# power_distribution_board_v3.net
KiCad netlist of a schematic drawn in EasyEDA
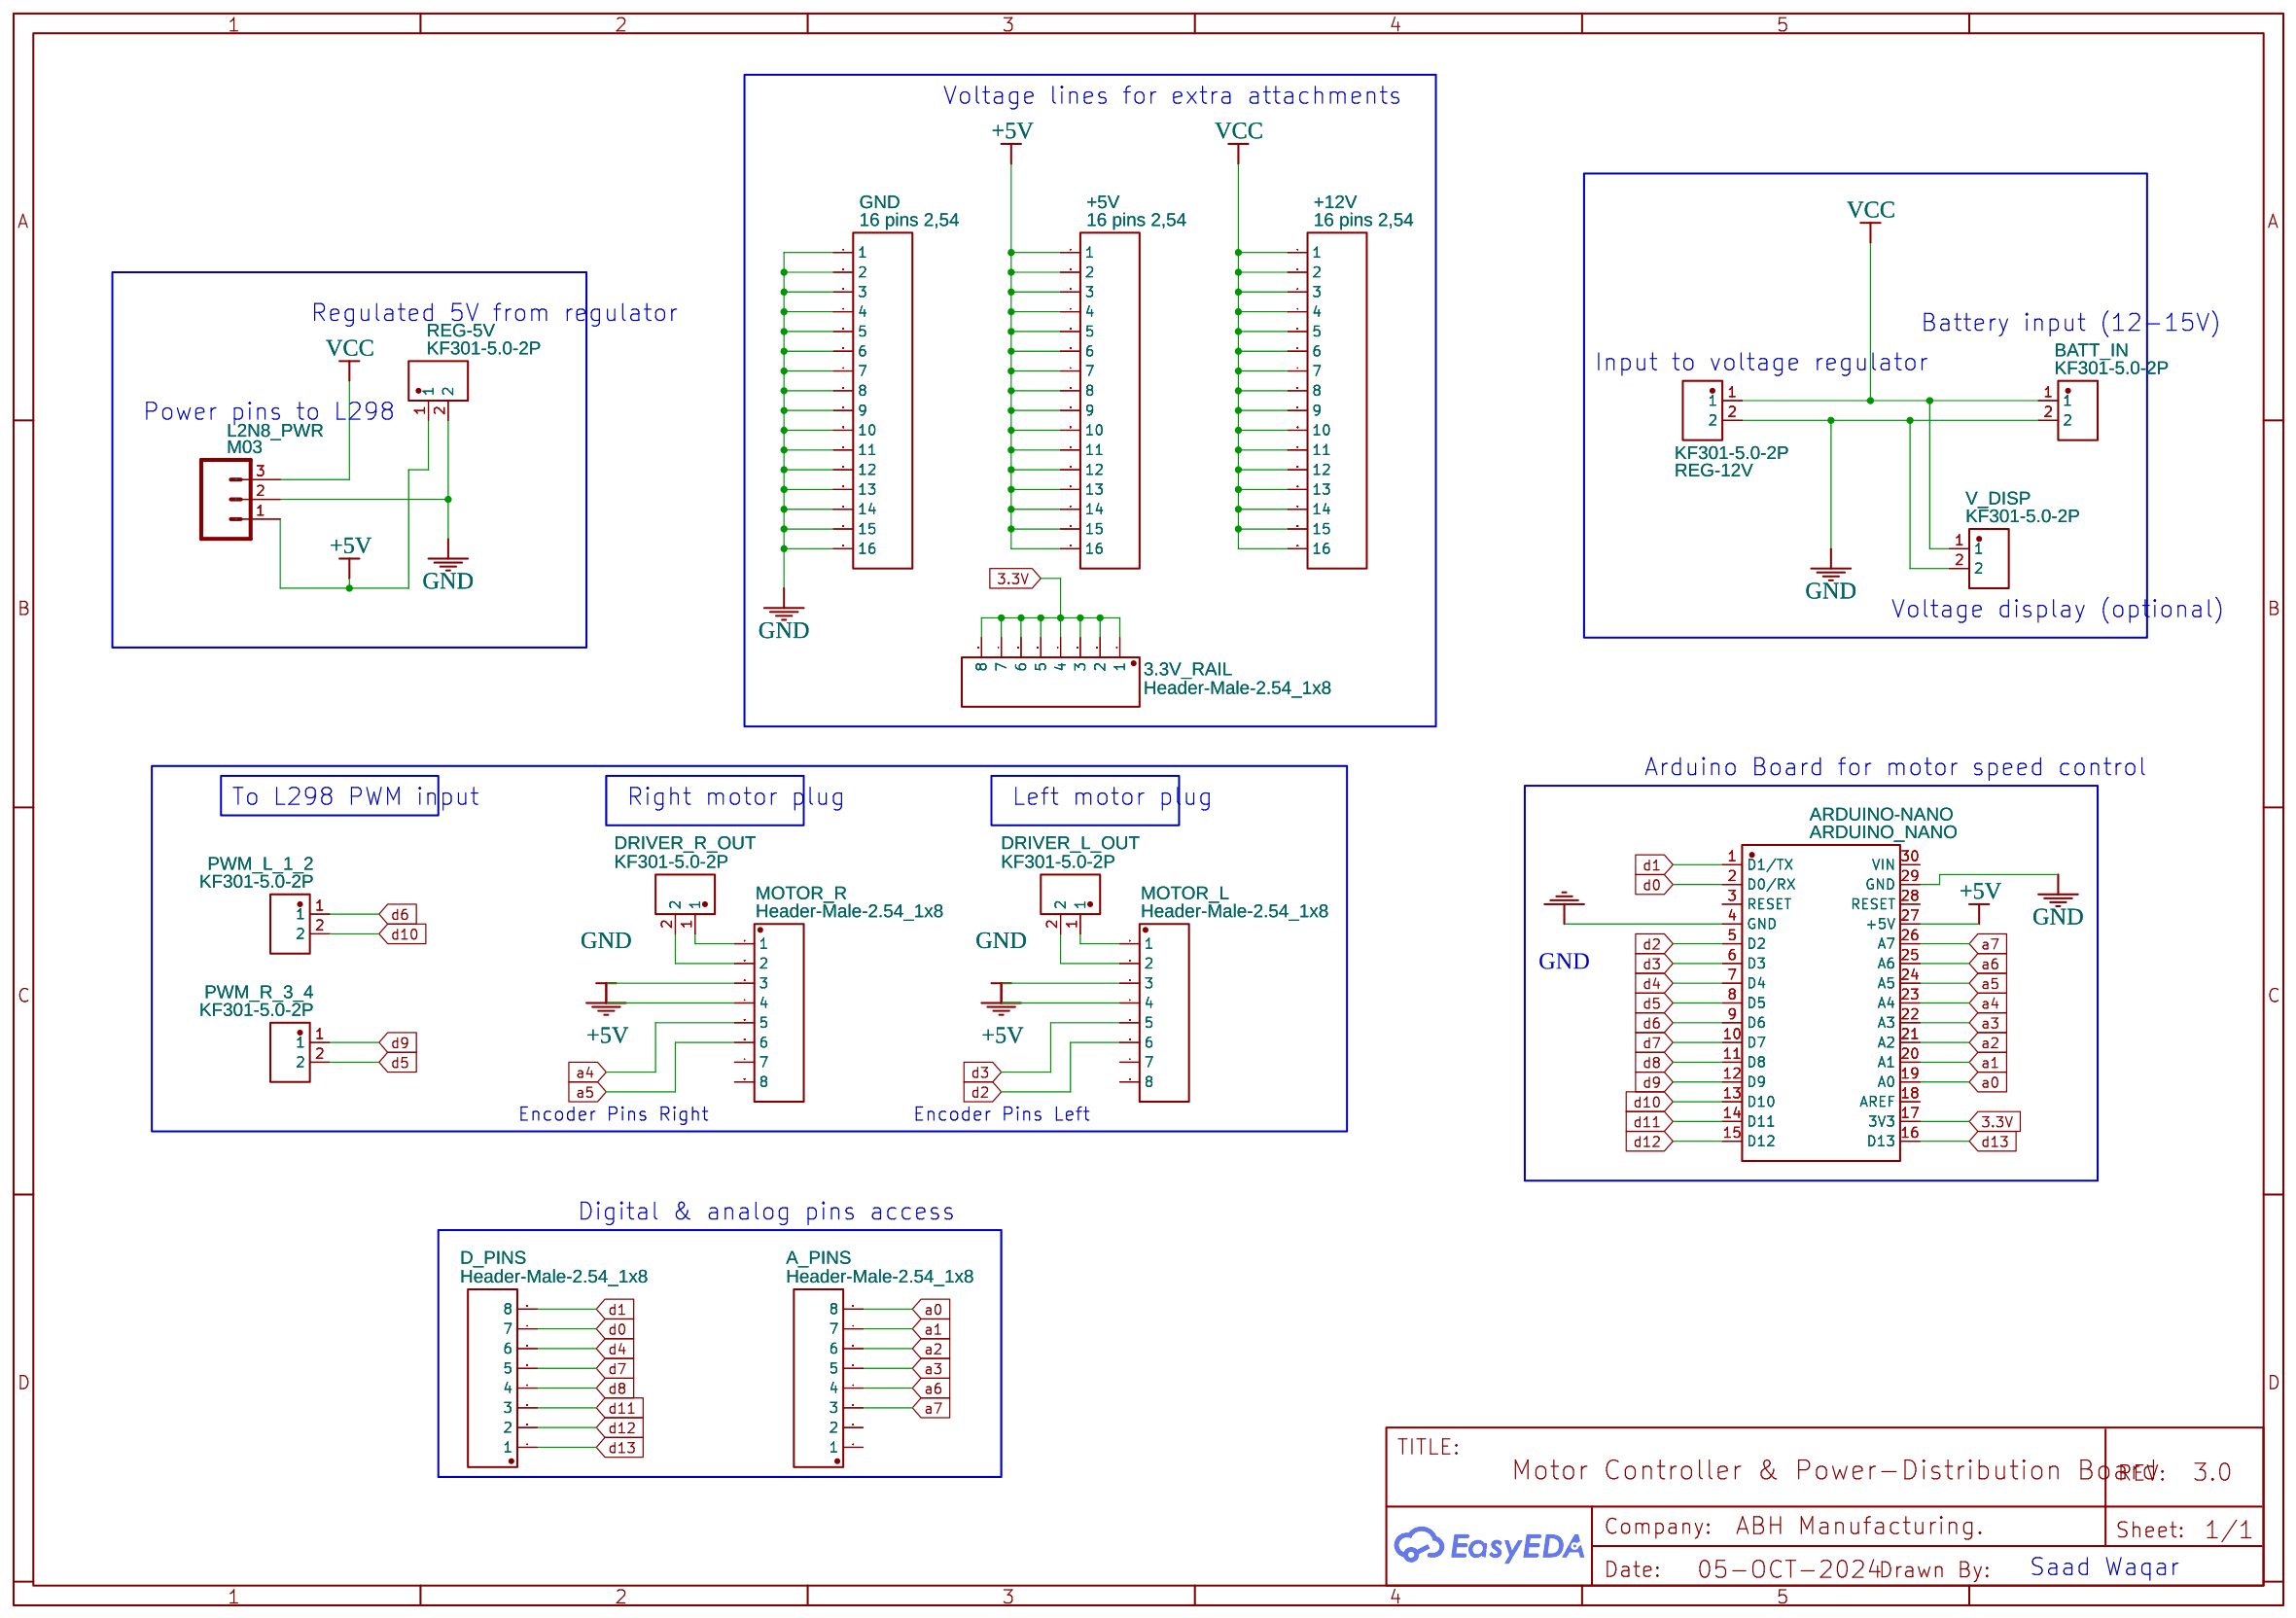
[diagram p0: schematic sheet]

(export (version "E")
  (design (tool "Eeschema 10.0.6"))
  (components
    (comp (ref "+5V") (value "16 pins 2,54") (libsource (lib "") (part "16 pins 2,54_1")))
    (comp (ref "+12V") (value "16 pins 2,54") (libsource (lib "") (part "16 pins 2,54_2")))
    (comp (ref "3.3V_RAIL")
      (value "Header-Male-2.54_1x8")
      (fields (field (name "Manufacturer Part") "B-2100S08P-A110") (field (name "Manufacturer") "Ckmtw(灿科盟)"))
      (libsource (lib "") (part "Header-Male-2.54_1x8_1"))
    )
    (comp (ref "ARDUINO-NANO") (value "ARDUINO_NANO") (libsource (lib "") (part "ARDUINO_NANO")))
    (comp (ref "A_PINS")
      (value "Header-Male-2.54_1x8")
      (fields (field (name "Manufacturer Part") "B-2100S08P-A110") (field (name "Manufacturer") "Ckmtw(灿科盟)"))
      (libsource (lib "") (part "Header-Male-2.54_1x8_2"))
    )
    (comp (ref "BATT_IN")
      (value "KF301-5.0-2P")
      (fields (field (name "Manufacturer") "KEFA(科发)"))
      (libsource (lib "") (part "KF301-5.0-2P_6"))
    )
    (comp (ref "DRIVER_L_OUT")
      (value "KF301-5.0-2P")
      (fields (field (name "Manufacturer") "KEFA(科发)"))
      (libsource (lib "") (part "KF301-5.0-2P_1"))
    )
    (comp (ref "DRIVER_R_OUT")
      (value "KF301-5.0-2P")
      (fields (field (name "Manufacturer") "KEFA(科发)"))
      (libsource (lib "") (part "KF301-5.0-2P_5"))
    )
    (comp (ref "D_PINS")
      (value "Header-Male-2.54_1x8")
      (fields (field (name "Manufacturer Part") "B-2100S08P-A110") (field (name "Manufacturer") "Ckmtw(灿科盟)"))
      (libsource (lib "") (part "Header-Male-2.54_1x8_4"))
    )
    (comp (ref "GND") (value "16 pins 2,54") (libsource (lib "") (part "16 pins 2,54")))
    (comp (ref "L2N8_PWR") (value "M03") (libsource (lib "") (part "M03")))
    (comp (ref "MOTOR_L")
      (value "Header-Male-2.54_1x8")
      (fields (field (name "Manufacturer Part") "B-2100S08P-A110") (field (name "Manufacturer") "Ckmtw(灿科盟)"))
      (libsource (lib "") (part "Header-Male-2.54_1x8_3"))
    )
    (comp (ref "MOTOR_R")
      (value "Header-Male-2.54_1x8")
      (fields (field (name "Manufacturer Part") "B-2100S08P-A110") (field (name "Manufacturer") "Ckmtw(灿科盟)"))
      (libsource (lib "") (part "Header-Male-2.54_1x8"))
    )
    (comp (ref "PWM_L_1_2")
      (value "KF301-5.0-2P")
      (fields (field (name "Manufacturer") "KEFA(科发)"))
      (libsource (lib "") (part "KF301-5.0-2P_2"))
    )
    (comp (ref "PWM_R_3_4")
      (value "KF301-5.0-2P")
      (fields (field (name "Manufacturer") "KEFA(科发)"))
      (libsource (lib "") (part "KF301-5.0-2P_4"))
    )
    (comp (ref "REG-5V")
      (value "KF301-5.0-2P")
      (fields (field (name "Manufacturer") "KEFA(科发)"))
      (libsource (lib "") (part "KF301-5.0-2P"))
    )
    (comp (ref "REG-12V")
      (value "KF301-5.0-2P")
      (fields (field (name "Manufacturer") "KEFA(科发)"))
      (libsource (lib "") (part "KF301-5.0-2P_3"))
    )
    (comp (ref "V_DISP")
      (value "KF301-5.0-2P")
      (fields (field (name "Manufacturer") "KEFA(科发)"))
      (libsource (lib "") (part "KF301-5.0-2P_7"))
    )
  )
  (nets
    (net (code "1") (name "+5V") (class "Default")
      (node (ref "+5V") (pin "1") (pinfunction "1_1") (pintype "input"))
      (node (ref "+5V") (pin "10") (pinfunction "10_10") (pintype "input"))
      (node (ref "+5V") (pin "11") (pinfunction "11_11") (pintype "input"))
      (node (ref "+5V") (pin "12") (pinfunction "12_12") (pintype "input"))
      (node (ref "+5V") (pin "13") (pinfunction "13_13") (pintype "input"))
      (node (ref "+5V") (pin "14") (pinfunction "14_14") (pintype "input"))
      (node (ref "+5V") (pin "15") (pinfunction "15_15") (pintype "input"))
      (node (ref "+5V") (pin "16") (pinfunction "16_16") (pintype "input"))
      (node (ref "+5V") (pin "2") (pinfunction "2_2") (pintype "input"))
      (node (ref "+5V") (pin "3") (pinfunction "3_3") (pintype "input"))
      (node (ref "+5V") (pin "4") (pinfunction "4_4") (pintype "input"))
      (node (ref "+5V") (pin "5") (pinfunction "5_5") (pintype "input"))
      (node (ref "+5V") (pin "6") (pinfunction "6_6") (pintype "input"))
      (node (ref "+5V") (pin "7") (pinfunction "7_7") (pintype "input"))
      (node (ref "+5V") (pin "8") (pinfunction "8_8") (pintype "input"))
      (node (ref "+5V") (pin "9") (pinfunction "9_9") (pintype "input"))
      (node (ref "ARDUINO-NANO") (pin "27") (pinfunction "+5V_27") (pintype "unspecified"))
      (node (ref "L2N8_PWR") (pin "1") (pinfunction "1_1") (pintype "unspecified"))
      (node (ref "MOTOR_L") (pin "4") (pinfunction "4_4") (pintype "unspecified"))
      (node (ref "MOTOR_R") (pin "4") (pinfunction "4_4") (pintype "unspecified"))
      (node (ref "REG-5V") (pin "1") (pinfunction "1_1") (pintype "unspecified"))
    )
    (net (code "2") (name "3.3V") (class "Default")
      (node (ref "3.3V_RAIL") (pin "1") (pinfunction "1_1") (pintype "unspecified"))
      (node (ref "3.3V_RAIL") (pin "2") (pinfunction "2_2") (pintype "unspecified"))
      (node (ref "3.3V_RAIL") (pin "3") (pinfunction "3_3") (pintype "unspecified"))
      (node (ref "3.3V_RAIL") (pin "4") (pinfunction "4_4") (pintype "unspecified"))
      (node (ref "3.3V_RAIL") (pin "5") (pinfunction "5_5") (pintype "unspecified"))
      (node (ref "3.3V_RAIL") (pin "6") (pinfunction "6_6") (pintype "unspecified"))
      (node (ref "3.3V_RAIL") (pin "7") (pinfunction "7_7") (pintype "unspecified"))
      (node (ref "3.3V_RAIL") (pin "8") (pinfunction "8_8") (pintype "unspecified"))
      (node (ref "ARDUINO-NANO") (pin "17") (pinfunction "3V3_17") (pintype "unspecified"))
    )
    (net (code "3") (name "GND") (class "Default")
      (node (ref "ARDUINO-NANO") (pin "29") (pinfunction "GND_29") (pintype "unspecified"))
      (node (ref "ARDUINO-NANO") (pin "4") (pinfunction "GND_4") (pintype "unspecified"))
      (node (ref "BATT_IN") (pin "2") (pinfunction "2_2") (pintype "unspecified"))
      (node (ref "GND") (pin "1") (pinfunction "1_1") (pintype "input"))
      (node (ref "GND") (pin "10") (pinfunction "10_10") (pintype "input"))
      (node (ref "GND") (pin "11") (pinfunction "11_11") (pintype "input"))
      (node (ref "GND") (pin "12") (pinfunction "12_12") (pintype "input"))
      (node (ref "GND") (pin "13") (pinfunction "13_13") (pintype "input"))
      (node (ref "GND") (pin "14") (pinfunction "14_14") (pintype "input"))
      (node (ref "GND") (pin "15") (pinfunction "15_15") (pintype "input"))
      (node (ref "GND") (pin "16") (pinfunction "16_16") (pintype "input"))
      (node (ref "GND") (pin "2") (pinfunction "2_2") (pintype "input"))
      (node (ref "GND") (pin "3") (pinfunction "3_3") (pintype "input"))
      (node (ref "GND") (pin "4") (pinfunction "4_4") (pintype "input"))
      (node (ref "GND") (pin "5") (pinfunction "5_5") (pintype "input"))
      (node (ref "GND") (pin "6") (pinfunction "6_6") (pintype "input"))
      (node (ref "GND") (pin "7") (pinfunction "7_7") (pintype "input"))
      (node (ref "GND") (pin "8") (pinfunction "8_8") (pintype "input"))
      (node (ref "GND") (pin "9") (pinfunction "9_9") (pintype "input"))
      (node (ref "L2N8_PWR") (pin "2") (pinfunction "2_2") (pintype "unspecified"))
      (node (ref "MOTOR_L") (pin "3") (pinfunction "3_3") (pintype "unspecified"))
      (node (ref "MOTOR_R") (pin "3") (pinfunction "3_3") (pintype "unspecified"))
      (node (ref "REG-12V") (pin "2") (pinfunction "2_2") (pintype "unspecified"))
      (node (ref "REG-5V") (pin "2") (pinfunction "2_2") (pintype "unspecified"))
      (node (ref "V_DISP") (pin "2") (pinfunction "2_2") (pintype "unspecified"))
    )
    (net (code "4") (name "Net-(DRIVER_L_OUT-Pad1)") (class "Default")
      (node (ref "DRIVER_L_OUT") (pin "1") (pinfunction "1_1") (pintype "unspecified"))
      (node (ref "MOTOR_L") (pin "1") (pinfunction "1_1") (pintype "unspecified"))
    )
    (net (code "5") (name "Net-(DRIVER_L_OUT-Pad2)") (class "Default")
      (node (ref "DRIVER_L_OUT") (pin "2") (pinfunction "2_2") (pintype "unspecified"))
      (node (ref "MOTOR_L") (pin "2") (pinfunction "2_2") (pintype "unspecified"))
    )
    (net (code "6") (name "Net-(DRIVER_R_OUT-Pad1)") (class "Default")
      (node (ref "DRIVER_R_OUT") (pin "1") (pinfunction "1_1") (pintype "unspecified"))
      (node (ref "MOTOR_R") (pin "1") (pinfunction "1_1") (pintype "unspecified"))
    )
    (net (code "7") (name "Net-(DRIVER_R_OUT-Pad2)") (class "Default")
      (node (ref "DRIVER_R_OUT") (pin "2") (pinfunction "2_2") (pintype "unspecified"))
      (node (ref "MOTOR_R") (pin "2") (pinfunction "2_2") (pintype "unspecified"))
    )
    (net (code "8") (name "VCC") (class "Default")
      (node (ref "+12V") (pin "1") (pinfunction "1_1") (pintype "input"))
      (node (ref "+12V") (pin "10") (pinfunction "10_10") (pintype "input"))
      (node (ref "+12V") (pin "11") (pinfunction "11_11") (pintype "input"))
      (node (ref "+12V") (pin "12") (pinfunction "12_12") (pintype "input"))
      (node (ref "+12V") (pin "13") (pinfunction "13_13") (pintype "input"))
      (node (ref "+12V") (pin "14") (pinfunction "14_14") (pintype "input"))
      (node (ref "+12V") (pin "15") (pinfunction "15_15") (pintype "input"))
      (node (ref "+12V") (pin "16") (pinfunction "16_16") (pintype "input"))
      (node (ref "+12V") (pin "2") (pinfunction "2_2") (pintype "input"))
      (node (ref "+12V") (pin "3") (pinfunction "3_3") (pintype "input"))
      (node (ref "+12V") (pin "4") (pinfunction "4_4") (pintype "input"))
      (node (ref "+12V") (pin "5") (pinfunction "5_5") (pintype "input"))
      (node (ref "+12V") (pin "6") (pinfunction "6_6") (pintype "input"))
      (node (ref "+12V") (pin "7") (pinfunction "7_7") (pintype "input"))
      (node (ref "+12V") (pin "8") (pinfunction "8_8") (pintype "input"))
      (node (ref "+12V") (pin "9") (pinfunction "9_9") (pintype "input"))
      (node (ref "BATT_IN") (pin "1") (pinfunction "1_1") (pintype "unspecified"))
      (node (ref "L2N8_PWR") (pin "3") (pinfunction "3_3") (pintype "unspecified"))
      (node (ref "REG-12V") (pin "1") (pinfunction "1_1") (pintype "unspecified"))
      (node (ref "V_DISP") (pin "1") (pinfunction "1_1") (pintype "unspecified"))
    )
    (net (code "9") (name "a0") (class "Default")
      (node (ref "ARDUINO-NANO") (pin "19") (pinfunction "A0_19") (pintype "unspecified"))
      (node (ref "A_PINS") (pin "8") (pinfunction "8_8") (pintype "unspecified"))
    )
    (net (code "10") (name "a1") (class "Default")
      (node (ref "ARDUINO-NANO") (pin "20") (pinfunction "A1_20") (pintype "unspecified"))
      (node (ref "A_PINS") (pin "7") (pinfunction "7_7") (pintype "unspecified"))
    )
    (net (code "11") (name "a2") (class "Default")
      (node (ref "ARDUINO-NANO") (pin "21") (pinfunction "A2_21") (pintype "unspecified"))
      (node (ref "A_PINS") (pin "6") (pinfunction "6_6") (pintype "unspecified"))
    )
    (net (code "12") (name "a3") (class "Default")
      (node (ref "ARDUINO-NANO") (pin "22") (pinfunction "A3_22") (pintype "unspecified"))
      (node (ref "A_PINS") (pin "5") (pinfunction "5_5") (pintype "unspecified"))
    )
    (net (code "13") (name "a4") (class "Default")
      (node (ref "ARDUINO-NANO") (pin "23") (pinfunction "A4_23") (pintype "unspecified"))
      (node (ref "MOTOR_R") (pin "5") (pinfunction "5_5") (pintype "unspecified"))
    )
    (net (code "14") (name "a5") (class "Default")
      (node (ref "ARDUINO-NANO") (pin "24") (pinfunction "A5_24") (pintype "unspecified"))
      (node (ref "MOTOR_R") (pin "6") (pinfunction "6_6") (pintype "unspecified"))
    )
    (net (code "15") (name "a6") (class "Default")
      (node (ref "ARDUINO-NANO") (pin "25") (pinfunction "A6_25") (pintype "unspecified"))
      (node (ref "A_PINS") (pin "4") (pinfunction "4_4") (pintype "unspecified"))
    )
    (net (code "16") (name "a7") (class "Default")
      (node (ref "ARDUINO-NANO") (pin "26") (pinfunction "A7_26") (pintype "unspecified"))
      (node (ref "A_PINS") (pin "3") (pinfunction "3_3") (pintype "unspecified"))
    )
    (net (code "17") (name "d0") (class "Default")
      (node (ref "ARDUINO-NANO") (pin "2") (pinfunction "D0/RX_2") (pintype "unspecified"))
      (node (ref "D_PINS") (pin "7") (pinfunction "7_7") (pintype "unspecified"))
    )
    (net (code "18") (name "d1") (class "Default")
      (node (ref "ARDUINO-NANO") (pin "1") (pinfunction "D1/TX_1") (pintype "unspecified"))
      (node (ref "D_PINS") (pin "8") (pinfunction "8_8") (pintype "unspecified"))
    )
    (net (code "19") (name "d2") (class "Default")
      (node (ref "ARDUINO-NANO") (pin "5") (pinfunction "D2_5") (pintype "unspecified"))
      (node (ref "MOTOR_L") (pin "6") (pinfunction "6_6") (pintype "unspecified"))
    )
    (net (code "20") (name "d3") (class "Default")
      (node (ref "ARDUINO-NANO") (pin "6") (pinfunction "D3_6") (pintype "unspecified"))
      (node (ref "MOTOR_L") (pin "5") (pinfunction "5_5") (pintype "unspecified"))
    )
    (net (code "21") (name "d4") (class "Default")
      (node (ref "ARDUINO-NANO") (pin "7") (pinfunction "D4_7") (pintype "unspecified"))
      (node (ref "D_PINS") (pin "6") (pinfunction "6_6") (pintype "unspecified"))
    )
    (net (code "22") (name "d5") (class "Default")
      (node (ref "ARDUINO-NANO") (pin "8") (pinfunction "D5_8") (pintype "unspecified"))
      (node (ref "PWM_R_3_4") (pin "2") (pinfunction "2_2") (pintype "unspecified"))
    )
    (net (code "23") (name "d6") (class "Default")
      (node (ref "ARDUINO-NANO") (pin "9") (pinfunction "D6_9") (pintype "unspecified"))
      (node (ref "PWM_L_1_2") (pin "1") (pinfunction "1_1") (pintype "unspecified"))
    )
    (net (code "24") (name "d7") (class "Default")
      (node (ref "ARDUINO-NANO") (pin "10") (pinfunction "D7_10") (pintype "unspecified"))
      (node (ref "D_PINS") (pin "5") (pinfunction "5_5") (pintype "unspecified"))
    )
    (net (code "25") (name "d8") (class "Default")
      (node (ref "ARDUINO-NANO") (pin "11") (pinfunction "D8_11") (pintype "unspecified"))
      (node (ref "D_PINS") (pin "4") (pinfunction "4_4") (pintype "unspecified"))
    )
    (net (code "26") (name "d9") (class "Default")
      (node (ref "ARDUINO-NANO") (pin "12") (pinfunction "D9_12") (pintype "unspecified"))
      (node (ref "PWM_R_3_4") (pin "1") (pinfunction "1_1") (pintype "unspecified"))
    )
    (net (code "27") (name "d10") (class "Default")
      (node (ref "ARDUINO-NANO") (pin "13") (pinfunction "D10_13") (pintype "unspecified"))
      (node (ref "PWM_L_1_2") (pin "2") (pinfunction "2_2") (pintype "unspecified"))
    )
    (net (code "28") (name "d11") (class "Default")
      (node (ref "ARDUINO-NANO") (pin "14") (pinfunction "D11_14") (pintype "unspecified"))
      (node (ref "D_PINS") (pin "3") (pinfunction "3_3") (pintype "unspecified"))
    )
    (net (code "29") (name "d12") (class "Default")
      (node (ref "ARDUINO-NANO") (pin "15") (pinfunction "D12_15") (pintype "unspecified"))
      (node (ref "D_PINS") (pin "2") (pinfunction "2_2") (pintype "unspecified"))
    )
    (net (code "30") (name "d13") (class "Default")
      (node (ref "ARDUINO-NANO") (pin "16") (pinfunction "D13_16") (pintype "unspecified"))
      (node (ref "D_PINS") (pin "1") (pinfunction "1_1") (pintype "unspecified"))
    )
    (net (code "31") (name "unconnected-(ARDUINO-NANO-AREF-Pad18)") (class "Default")
      (node (ref "ARDUINO-NANO") (pin "18") (pinfunction "AREF_18") (pintype "unspecified"))
    )
    (net (code "32") (name "unconnected-(ARDUINO-NANO-RESET-Pad3)") (class "Default")
      (node (ref "ARDUINO-NANO") (pin "3") (pinfunction "RESET_3") (pintype "unspecified"))
    )
    (net (code "33") (name "unconnected-(ARDUINO-NANO-RESET-Pad28)") (class "Default")
      (node (ref "ARDUINO-NANO") (pin "28") (pinfunction "RESET_28") (pintype "unspecified"))
    )
    (net (code "34") (name "unconnected-(ARDUINO-NANO-VIN-Pad30)") (class "Default")
      (node (ref "ARDUINO-NANO") (pin "30") (pinfunction "VIN_30") (pintype "unspecified"))
    )
    (net (code "35") (name "unconnected-(A_PINS-Pad1)") (class "Default")
      (node (ref "A_PINS") (pin "1") (pinfunction "1_1") (pintype "unspecified"))
    )
    (net (code "36") (name "unconnected-(A_PINS-Pad2)") (class "Default")
      (node (ref "A_PINS") (pin "2") (pinfunction "2_2") (pintype "unspecified"))
    )
    (net (code "37") (name "unconnected-(MOTOR_L-Pad7)") (class "Default")
      (node (ref "MOTOR_L") (pin "7") (pinfunction "7_7") (pintype "unspecified"))
    )
    (net (code "38") (name "unconnected-(MOTOR_L-Pad8)") (class "Default")
      (node (ref "MOTOR_L") (pin "8") (pinfunction "8_8") (pintype "unspecified"))
    )
    (net (code "39") (name "unconnected-(MOTOR_R-Pad7)") (class "Default")
      (node (ref "MOTOR_R") (pin "7") (pinfunction "7_7") (pintype "unspecified"))
    )
    (net (code "40") (name "unconnected-(MOTOR_R-Pad8)") (class "Default")
      (node (ref "MOTOR_R") (pin "8") (pinfunction "8_8") (pintype "unspecified"))
    )
  )
)
